# TMP100NA_temp_sensor.net
KiCad netlist of a schematic drawn in Altium Designer
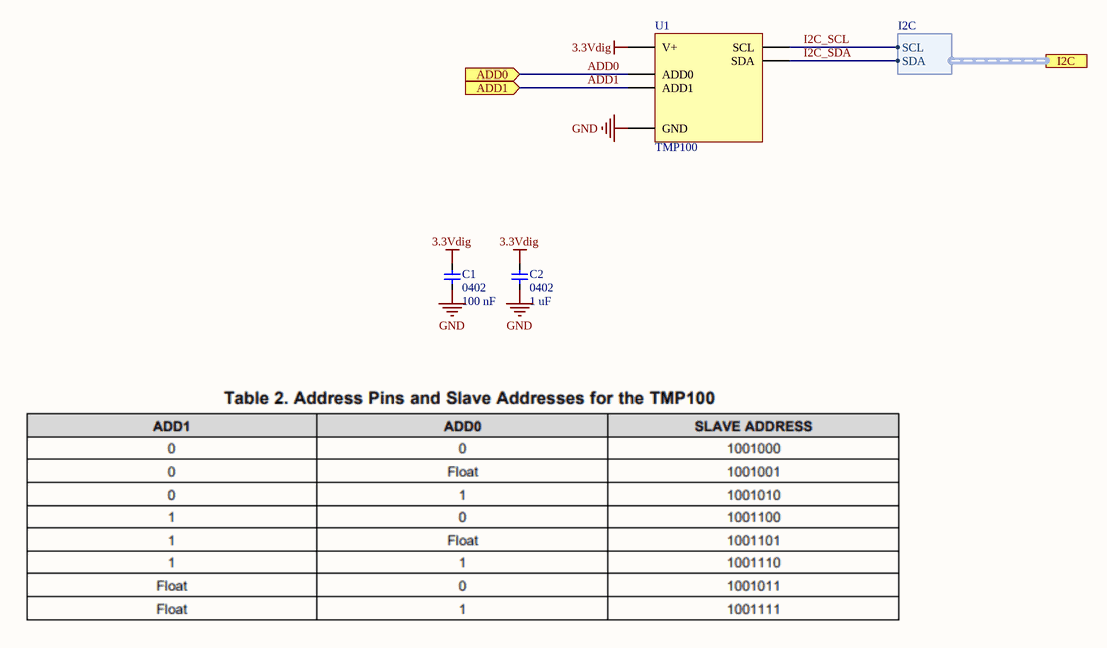
[diagram p0: TMP100NA_temp_sensor.SchDoc]

(export (version "E")
  (design (tool "Eeschema 10.0.6"))
  (components
    (comp (ref "C1")
      (value "0402")
      (footprint "CAPCERSMD0402")
      (fields (field (name "ALTIUM_VALUE") "100 nF"))
      (libsource (lib "0402_Cap_Cer__SARAversion-24") (part "CAPCER0402_X7R_50V_100n"))
    )
    (comp (ref "C2")
      (value "0402")
      (footprint "CAPCERSMD0402")
      (fields (field (name "ALTIUM_VALUE") "1 uF"))
      (libsource (lib "0402_Cap_Cer__SARAversion-24") (part "CAPCER0402_X5R_10V_1u"))
    )
    (comp (ref "U1")
      (value "TMP100")
      (footprint "SOT6_P95W280L290H145")
      (libsource (lib "Sensors__SARAversion-39") (part "TMP100NA/250"))
    )
  )
  (nets
    (net (code "2") (name "/ADD0") (class "Default")
      (node (ref "U1") (pin "5") (pinfunction "ADD0_5") (pintype "passive"))
    )
    (net (code "3") (name "/ADD1") (class "Default")
      (node (ref "U1") (pin "3") (pinfunction "ADD1_3") (pintype "passive"))
    )
    (net (code "4") (name "/I2C_SCL") (class "Default")
      (node (ref "U1") (pin "1") (pinfunction "SCL_1") (pintype "passive"))
    )
    (net (code "5") (name "/I2C_SDA") (class "Default")
      (node (ref "U1") (pin "6") (pinfunction "SDA_6") (pintype "passive"))
    )
    (net (code "7") (name "3.3Vdig") (class "Default")
      (node (ref "C1") (pin "2") (pinfunction "2_2") (pintype "passive"))
      (node (ref "C2") (pin "2") (pinfunction "2_2") (pintype "passive"))
      (node (ref "U1") (pin "4") (pinfunction "V+_4") (pintype "passive"))
    )
    (net (code "8") (name "GND") (class "Default")
      (node (ref "C1") (pin "1") (pinfunction "1_1") (pintype "passive"))
      (node (ref "C2") (pin "1") (pinfunction "1_1") (pintype "passive"))
      (node (ref "U1") (pin "2") (pinfunction "GND_2") (pintype "passive"))
    )
  )
)
